# mobo-dual-boards.net
KiCad netlist of a schematic drawn in EAGLE
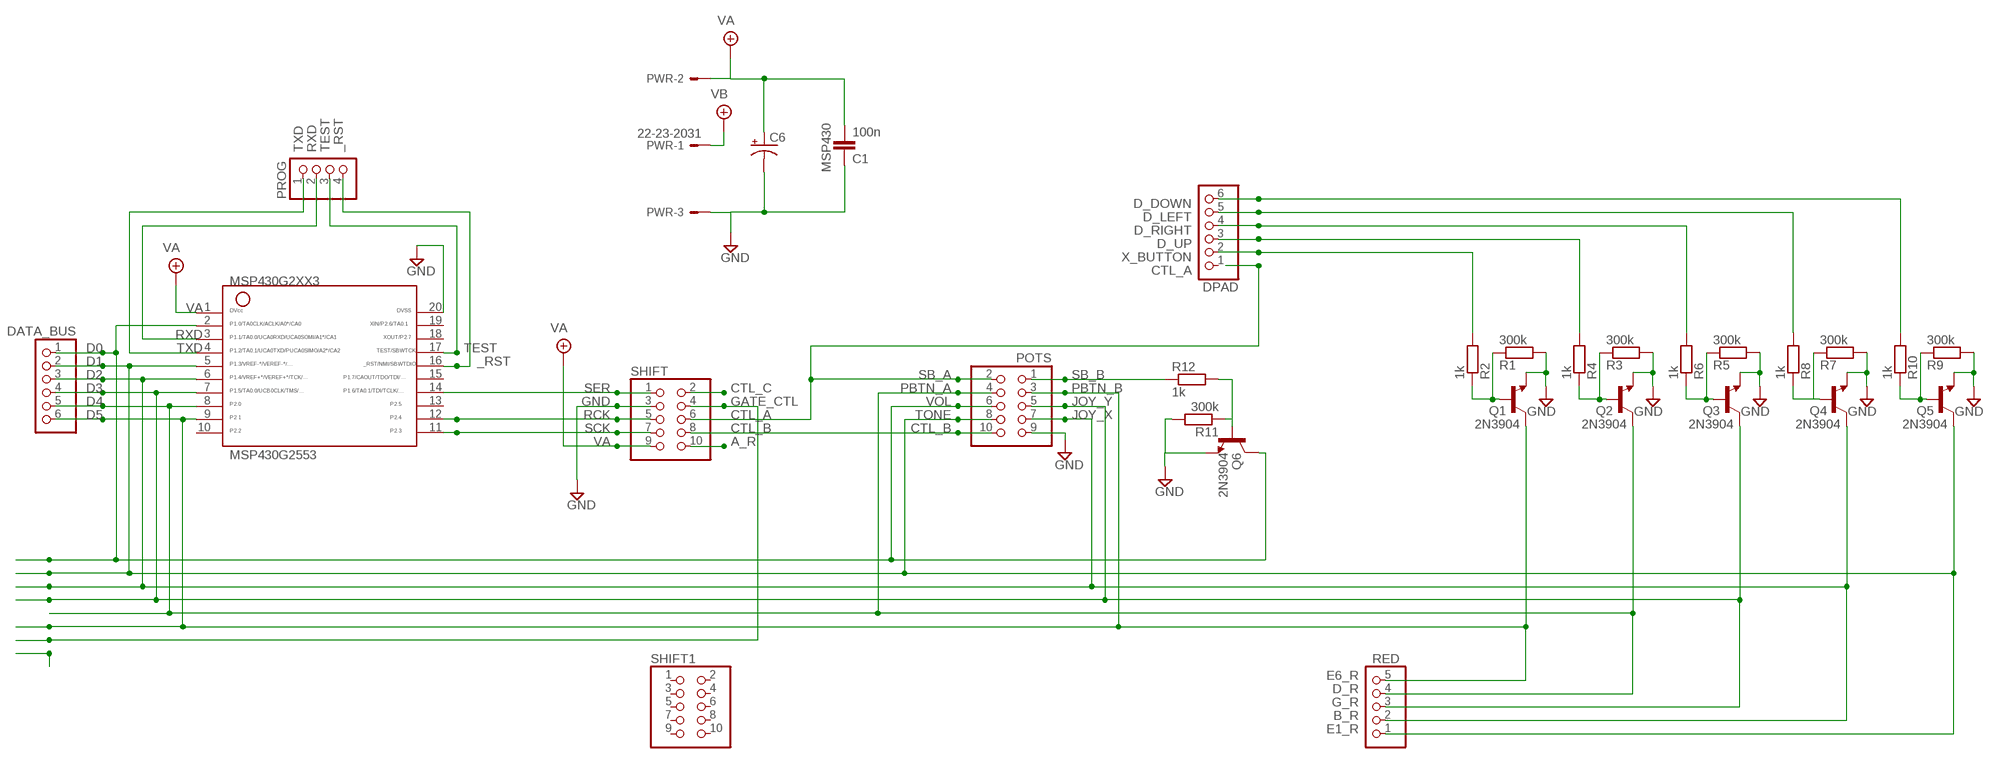
[diagram p0: schematic, sheet 1]

(export (version "E")
  (design (tool "Eeschema 10.0.6"))
  (components
    (comp (ref "C1")
      (value "100n")
      (footprint "eagle-import:050X030_050_3")
      (libsource (lib "eagle-import") (part "050X030_050"))
    )
    (comp (ref "C6")
      (value "0501")
      (footprint "eagle-import:050_020_1")
      (libsource (lib "eagle-import") (part "0501"))
    )
    (comp (ref "DATA_BUS")
      (value "PINHD-1X6")
      (footprint "eagle-import:1X06")
      (libsource (lib "eagle-import") (part "PINHD-1X6"))
    )
    (comp (ref "DPAD")
      (value "PINHD-1X6")
      (footprint "eagle-import:1X06")
      (libsource (lib "eagle-import") (part "PINHD-1X6"))
    )
    (comp (ref "MSP430G2553")
      (value "G2XX3---N20")
      (footprint "eagle-import:N20")
      (libsource (lib "eagle-import") (part "G2XX3---N20"))
    )
    (comp (ref "POTS")
      (value "PINHD-2X5")
      (footprint "eagle-import:2X05")
      (libsource (lib "eagle-import") (part "PINHD-2X5"))
    )
    (comp (ref "PROG")
      (value "PINHD-1X4")
      (footprint "eagle-import:1X04")
      (libsource (lib "eagle-import") (part "PINHD-1X4"))
    )
    (comp (ref "PWR")
      (value "22-23-2031")
      (footprint "eagle-import:22-23-2031")
      (fields (field (name "MF") "MOLEX"))
      (libsource (lib "eagle-import") (part "22-23-2031"))
    )
    (comp (ref "Q1")
      (value "2N3904")
      (footprint "eagle-import:TO92-")
      (libsource (lib "eagle-import") (part "2N3904"))
    )
    (comp (ref "Q2")
      (value "2N3904")
      (footprint "eagle-import:TO92-")
      (libsource (lib "eagle-import") (part "2N3904"))
    )
    (comp (ref "Q3")
      (value "2N3904")
      (footprint "eagle-import:TO92-")
      (libsource (lib "eagle-import") (part "2N3904"))
    )
    (comp (ref "Q4")
      (value "2N3904")
      (footprint "eagle-import:TO92-")
      (libsource (lib "eagle-import") (part "2N3904"))
    )
    (comp (ref "Q5")
      (value "2N3904")
      (footprint "eagle-import:TO92-")
      (libsource (lib "eagle-import") (part "2N3904"))
    )
    (comp (ref "Q6")
      (value "2N3904")
      (footprint "eagle-import:TO92-")
      (libsource (lib "eagle-import") (part "2N3904"))
    )
    (comp (ref "R1")
      (value "300k")
      (footprint "eagle-import:R0207_1V")
      (libsource (lib "eagle-import") (part "6MM-EU1"))
    )
    (comp (ref "R2")
      (value "1k")
      (footprint "eagle-import:R0207_1V")
      (libsource (lib "eagle-import") (part "6MM-EU1"))
    )
    (comp (ref "R3")
      (value "300k")
      (footprint "eagle-import:R0207_1V")
      (libsource (lib "eagle-import") (part "6MM-EU1"))
    )
    (comp (ref "R4")
      (value "1k")
      (footprint "eagle-import:R0207_1V")
      (libsource (lib "eagle-import") (part "6MM-EU1"))
    )
    (comp (ref "R5")
      (value "300k")
      (footprint "eagle-import:R0207_1V")
      (libsource (lib "eagle-import") (part "6MM-EU1"))
    )
    (comp (ref "R6")
      (value "1k")
      (footprint "eagle-import:R0207_1V")
      (libsource (lib "eagle-import") (part "6MM-EU1"))
    )
    (comp (ref "R7")
      (value "300k")
      (footprint "eagle-import:R0207_1V")
      (libsource (lib "eagle-import") (part "6MM-EU1"))
    )
    (comp (ref "R8")
      (value "1k")
      (footprint "eagle-import:R0207_1V")
      (libsource (lib "eagle-import") (part "6MM-EU1"))
    )
    (comp (ref "R9")
      (value "300k")
      (footprint "eagle-import:R0207_1V")
      (libsource (lib "eagle-import") (part "6MM-EU1"))
    )
    (comp (ref "R10")
      (value "1k")
      (footprint "eagle-import:R0207_1V")
      (libsource (lib "eagle-import") (part "6MM-EU1"))
    )
    (comp (ref "R11")
      (value "300k")
      (footprint "eagle-import:R0207_1V")
      (libsource (lib "eagle-import") (part "6MM-EU1"))
    )
    (comp (ref "R12")
      (value "1k")
      (footprint "eagle-import:R0207_1V")
      (libsource (lib "eagle-import") (part "6MM-EU1"))
    )
    (comp (ref "RED")
      (value "PINHD-1X5")
      (footprint "eagle-import:1X05")
      (libsource (lib "eagle-import") (part "PINHD-1X5"))
    )
    (comp (ref "SHIFT")
      (value "PINHD-2X5")
      (footprint "eagle-import:2X05")
      (libsource (lib "eagle-import") (part "PINHD-2X5"))
    )
    (comp (ref "SHIFT1")
      (value "PINHD-2X5")
      (footprint "eagle-import:2X05")
      (libsource (lib "eagle-import") (part "PINHD-2X5"))
    )
  )
  (nets
    (net (code "1") (name "/CTL_A") (class "Default")
      (node (ref "POTS") (pin "2") (pinfunction "2_2") (pintype "passive"))
      (node (ref "SHIFT") (pin "6") (pinfunction "6_6") (pintype "passive"))
    )
    (net (code "2") (name "/CTL_B") (class "Default")
      (node (ref "POTS") (pin "10") (pinfunction "10_10") (pintype "passive"))
      (node (ref "SHIFT") (pin "8") (pinfunction "8_8") (pintype "passive"))
    )
    (net (code "3") (name "/CTL_C") (class "Default")
      (node (ref "SHIFT") (pin "2") (pinfunction "2_2") (pintype "passive"))
    )
    (net (code "4") (name "/D0") (class "Default")
      (node (ref "DATA_BUS") (pin "1") (pinfunction "1_1") (pintype "passive"))
      (node (ref "MSP430G2553") (pin "2") (pinfunction "2_2") (pintype "bidirectional"))
      (node (ref "POTS") (pin "6") (pinfunction "6_6") (pintype "passive"))
      (node (ref "Q6") (pin "1") (pinfunction "C_1") (pintype "passive"))
      (node (ref "SHIFT") (pin "10") (pinfunction "10_10") (pintype "passive"))
    )
    (net (code "5") (name "/D1") (class "Default")
      (node (ref "DATA_BUS") (pin "2") (pinfunction "2_2") (pintype "passive"))
      (node (ref "MSP430G2553") (pin "5") (pinfunction "5_5") (pintype "bidirectional"))
      (node (ref "POTS") (pin "8") (pinfunction "8_8") (pintype "passive"))
      (node (ref "Q5") (pin "1") (pinfunction "C_1") (pintype "passive"))
      (node (ref "RED") (pin "1") (pinfunction "1_1") (pintype "passive"))
    )
    (net (code "6") (name "/D2") (class "Default")
      (node (ref "DATA_BUS") (pin "3") (pinfunction "3_3") (pintype "passive"))
      (node (ref "MSP430G2553") (pin "6") (pinfunction "6_6") (pintype "bidirectional"))
      (node (ref "POTS") (pin "7") (pinfunction "7_7") (pintype "passive"))
      (node (ref "Q4") (pin "1") (pinfunction "C_1") (pintype "passive"))
      (node (ref "RED") (pin "2") (pinfunction "2_2") (pintype "passive"))
    )
    (net (code "7") (name "/D3") (class "Default")
      (node (ref "DATA_BUS") (pin "4") (pinfunction "4_4") (pintype "passive"))
      (node (ref "MSP430G2553") (pin "7") (pinfunction "7_7") (pintype "bidirectional"))
      (node (ref "POTS") (pin "5") (pinfunction "5_5") (pintype "passive"))
      (node (ref "Q3") (pin "1") (pinfunction "C_1") (pintype "passive"))
      (node (ref "RED") (pin "3") (pinfunction "3_3") (pintype "passive"))
    )
    (net (code "8") (name "/D4") (class "Default")
      (node (ref "DATA_BUS") (pin "5") (pinfunction "5_5") (pintype "passive"))
      (node (ref "MSP430G2553") (pin "8") (pinfunction "8_8") (pintype "bidirectional"))
      (node (ref "POTS") (pin "4") (pinfunction "4_4") (pintype "passive"))
      (node (ref "Q2") (pin "1") (pinfunction "C_1") (pintype "passive"))
      (node (ref "RED") (pin "4") (pinfunction "4_4") (pintype "passive"))
    )
    (net (code "9") (name "/D5") (class "Default")
      (node (ref "DATA_BUS") (pin "6") (pinfunction "6_6") (pintype "passive"))
      (node (ref "MSP430G2553") (pin "9") (pinfunction "9_9") (pintype "bidirectional"))
      (node (ref "POTS") (pin "3") (pinfunction "3_3") (pintype "passive"))
      (node (ref "Q1") (pin "1") (pinfunction "C_1") (pintype "passive"))
      (node (ref "RED") (pin "5") (pinfunction "5_5") (pintype "passive"))
    )
    (net (code "10") (name "/D_DOWN") (class "Default")
      (node (ref "DPAD") (pin "6") (pinfunction "6_6") (pintype "passive"))
      (node (ref "R10") (pin "2") (pinfunction "2_2") (pintype "passive"))
    )
    (net (code "11") (name "/D_LEFT") (class "Default")
      (node (ref "DPAD") (pin "5") (pinfunction "5_5") (pintype "passive"))
      (node (ref "R8") (pin "2") (pinfunction "2_2") (pintype "passive"))
    )
    (net (code "12") (name "/D_RIGHT") (class "Default")
      (node (ref "DPAD") (pin "4") (pinfunction "4_4") (pintype "passive"))
      (node (ref "R6") (pin "2") (pinfunction "2_2") (pintype "passive"))
    )
    (net (code "13") (name "/D_UP") (class "Default")
      (node (ref "DPAD") (pin "3") (pinfunction "3_3") (pintype "passive"))
      (node (ref "R4") (pin "2") (pinfunction "2_2") (pintype "passive"))
    )
    (net (code "14") (name "/GATE_CTL") (class "Default")
      (node (ref "SHIFT") (pin "4") (pinfunction "4_4") (pintype "passive"))
    )
    (net (code "15") (name "/RCK") (class "Default")
      (node (ref "MSP430G2553") (pin "12") (pinfunction "12_12") (pintype "bidirectional"))
      (node (ref "SHIFT") (pin "5") (pinfunction "5_5") (pintype "passive"))
    )
    (net (code "16") (name "/RXD") (class "Default")
      (node (ref "MSP430G2553") (pin "3") (pinfunction "3_3") (pintype "bidirectional"))
      (node (ref "PROG") (pin "2") (pinfunction "2_2") (pintype "passive"))
    )
    (net (code "17") (name "/SCK") (class "Default")
      (node (ref "MSP430G2553") (pin "11") (pinfunction "11_11") (pintype "bidirectional"))
      (node (ref "SHIFT") (pin "7") (pinfunction "7_7") (pintype "passive"))
    )
    (net (code "18") (name "/SER") (class "Default")
      (node (ref "MSP430G2553") (pin "14") (pinfunction "14_14") (pintype "bidirectional"))
      (node (ref "SHIFT") (pin "1") (pinfunction "1_1") (pintype "passive"))
    )
    (net (code "19") (name "/TEST") (class "Default")
      (node (ref "MSP430G2553") (pin "17") (pinfunction "17_17") (pintype "bidirectional"))
      (node (ref "PROG") (pin "3") (pinfunction "3_3") (pintype "passive"))
    )
    (net (code "20") (name "/TXD") (class "Default")
      (node (ref "MSP430G2553") (pin "4") (pinfunction "4_4") (pintype "bidirectional"))
      (node (ref "PROG") (pin "1") (pinfunction "1_1") (pintype "passive"))
    )
    (net (code "21") (name "/X_BUTTON") (class "Default")
      (node (ref "DPAD") (pin "2") (pinfunction "2_2") (pintype "passive"))
      (node (ref "R2") (pin "2") (pinfunction "2_2") (pintype "passive"))
    )
    (net (code "22") (name "/_RST") (class "Default")
      (node (ref "MSP430G2553") (pin "16") (pinfunction "16_16") (pintype "bidirectional"))
      (node (ref "PROG") (pin "4") (pinfunction "4_4") (pintype "passive"))
    )
    (net (code "23") (name "GND") (class "Default")
      (node (ref "C1") (pin "1") (pinfunction "1_1") (pintype "passive"))
      (node (ref "C6") (pin "-") (pinfunction "-_-") (pintype "passive"))
      (node (ref "MSP430G2553") (pin "20") (pinfunction "20_20") (pintype "bidirectional"))
      (node (ref "POTS") (pin "9") (pinfunction "9_9") (pintype "passive"))
      (node (ref "PWR") (pin "3") (pinfunction "S_3") (pintype "passive"))
      (node (ref "Q1") (pin "3") (pinfunction "E_3") (pintype "passive"))
      (node (ref "Q2") (pin "3") (pinfunction "E_3") (pintype "passive"))
      (node (ref "Q3") (pin "3") (pinfunction "E_3") (pintype "passive"))
      (node (ref "Q4") (pin "3") (pinfunction "E_3") (pintype "passive"))
      (node (ref "Q5") (pin "3") (pinfunction "E_3") (pintype "passive"))
      (node (ref "Q6") (pin "3") (pinfunction "E_3") (pintype "passive"))
      (node (ref "R1") (pin "2") (pinfunction "2_2") (pintype "passive"))
      (node (ref "R11") (pin "2") (pinfunction "2_2") (pintype "passive"))
      (node (ref "R3") (pin "2") (pinfunction "2_2") (pintype "passive"))
      (node (ref "R5") (pin "2") (pinfunction "2_2") (pintype "passive"))
      (node (ref "R7") (pin "2") (pinfunction "2_2") (pintype "passive"))
      (node (ref "R9") (pin "2") (pinfunction "2_2") (pintype "passive"))
      (node (ref "SHIFT") (pin "3") (pinfunction "3_3") (pintype "passive"))
    )
    (net (code "24") (name "Net-(POTS-Pad1)") (class "Default")
      (node (ref "POTS") (pin "1") (pinfunction "1_1") (pintype "passive"))
      (node (ref "R12") (pin "1") (pinfunction "1_1") (pintype "passive"))
    )
    (net (code "25") (name "Net-(Q1-B)") (class "Default")
      (node (ref "Q1") (pin "2") (pinfunction "B_2") (pintype "passive"))
      (node (ref "R1") (pin "1") (pinfunction "1_1") (pintype "passive"))
      (node (ref "R2") (pin "1") (pinfunction "1_1") (pintype "passive"))
    )
    (net (code "26") (name "Net-(Q2-B)") (class "Default")
      (node (ref "Q2") (pin "2") (pinfunction "B_2") (pintype "passive"))
      (node (ref "R3") (pin "1") (pinfunction "1_1") (pintype "passive"))
      (node (ref "R4") (pin "1") (pinfunction "1_1") (pintype "passive"))
    )
    (net (code "27") (name "Net-(Q3-B)") (class "Default")
      (node (ref "Q3") (pin "2") (pinfunction "B_2") (pintype "passive"))
      (node (ref "R5") (pin "1") (pinfunction "1_1") (pintype "passive"))
      (node (ref "R6") (pin "1") (pinfunction "1_1") (pintype "passive"))
    )
    (net (code "28") (name "Net-(Q4-B)") (class "Default")
      (node (ref "Q4") (pin "2") (pinfunction "B_2") (pintype "passive"))
      (node (ref "R7") (pin "1") (pinfunction "1_1") (pintype "passive"))
      (node (ref "R8") (pin "1") (pinfunction "1_1") (pintype "passive"))
    )
    (net (code "29") (name "Net-(Q5-B)") (class "Default")
      (node (ref "Q5") (pin "2") (pinfunction "B_2") (pintype "passive"))
      (node (ref "R10") (pin "1") (pinfunction "1_1") (pintype "passive"))
      (node (ref "R9") (pin "1") (pinfunction "1_1") (pintype "passive"))
    )
    (net (code "30") (name "Net-(Q6-B)") (class "Default")
      (node (ref "Q6") (pin "2") (pinfunction "B_2") (pintype "passive"))
      (node (ref "R11") (pin "1") (pinfunction "1_1") (pintype "passive"))
      (node (ref "R12") (pin "2") (pinfunction "2_2") (pintype "passive"))
    )
    (net (code "31") (name "VA") (class "Default")
      (node (ref "C1") (pin "2") (pinfunction "2_2") (pintype "passive"))
      (node (ref "C6") (pin "+") (pinfunction "+_+") (pintype "passive"))
      (node (ref "MSP430G2553") (pin "1") (pinfunction "1_1") (pintype "bidirectional"))
      (node (ref "PWR") (pin "2") (pinfunction "S_2") (pintype "passive"))
      (node (ref "SHIFT") (pin "9") (pinfunction "9_9") (pintype "passive"))
    )
    (net (code "32") (name "VB") (class "Default")
      (node (ref "PWR") (pin "1") (pinfunction "S_1") (pintype "passive"))
    )
    (net (code "33") (name "unconnected-(DPAD-Pad1)") (class "Default")
      (node (ref "DPAD") (pin "1") (pinfunction "1_1") (pintype "passive"))
    )
    (net (code "34") (name "unconnected-(MSP430G2553-Pad10)") (class "Default")
      (node (ref "MSP430G2553") (pin "10") (pinfunction "10_10") (pintype "bidirectional"))
    )
    (net (code "35") (name "unconnected-(MSP430G2553-Pad13)") (class "Default")
      (node (ref "MSP430G2553") (pin "13") (pinfunction "13_13") (pintype "bidirectional"))
    )
    (net (code "36") (name "unconnected-(MSP430G2553-Pad15)") (class "Default")
      (node (ref "MSP430G2553") (pin "15") (pinfunction "15_15") (pintype "bidirectional"))
    )
    (net (code "37") (name "unconnected-(MSP430G2553-Pad18)") (class "Default")
      (node (ref "MSP430G2553") (pin "18") (pinfunction "18_18") (pintype "bidirectional"))
    )
    (net (code "38") (name "unconnected-(MSP430G2553-Pad19)") (class "Default")
      (node (ref "MSP430G2553") (pin "19") (pinfunction "19_19") (pintype "bidirectional"))
    )
    (net (code "39") (name "unconnected-(SHIFT1-Pad1)") (class "Default")
      (node (ref "SHIFT1") (pin "1") (pinfunction "1_1") (pintype "passive"))
    )
    (net (code "40") (name "unconnected-(SHIFT1-Pad2)") (class "Default")
      (node (ref "SHIFT1") (pin "2") (pinfunction "2_2") (pintype "passive"))
    )
    (net (code "41") (name "unconnected-(SHIFT1-Pad3)") (class "Default")
      (node (ref "SHIFT1") (pin "3") (pinfunction "3_3") (pintype "passive"))
    )
    (net (code "42") (name "unconnected-(SHIFT1-Pad4)") (class "Default")
      (node (ref "SHIFT1") (pin "4") (pinfunction "4_4") (pintype "passive"))
    )
    (net (code "43") (name "unconnected-(SHIFT1-Pad5)") (class "Default")
      (node (ref "SHIFT1") (pin "5") (pinfunction "5_5") (pintype "passive"))
    )
    (net (code "44") (name "unconnected-(SHIFT1-Pad6)") (class "Default")
      (node (ref "SHIFT1") (pin "6") (pinfunction "6_6") (pintype "passive"))
    )
    (net (code "45") (name "unconnected-(SHIFT1-Pad7)") (class "Default")
      (node (ref "SHIFT1") (pin "7") (pinfunction "7_7") (pintype "passive"))
    )
    (net (code "46") (name "unconnected-(SHIFT1-Pad8)") (class "Default")
      (node (ref "SHIFT1") (pin "8") (pinfunction "8_8") (pintype "passive"))
    )
    (net (code "47") (name "unconnected-(SHIFT1-Pad9)") (class "Default")
      (node (ref "SHIFT1") (pin "9") (pinfunction "9_9") (pintype "passive"))
    )
    (net (code "48") (name "unconnected-(SHIFT1-Pad10)") (class "Default")
      (node (ref "SHIFT1") (pin "10") (pinfunction "10_10") (pintype "passive"))
    )
  )
)
